# User_Control_Interface.net
KiCad netlist of a schematic drawn in Altium Designer
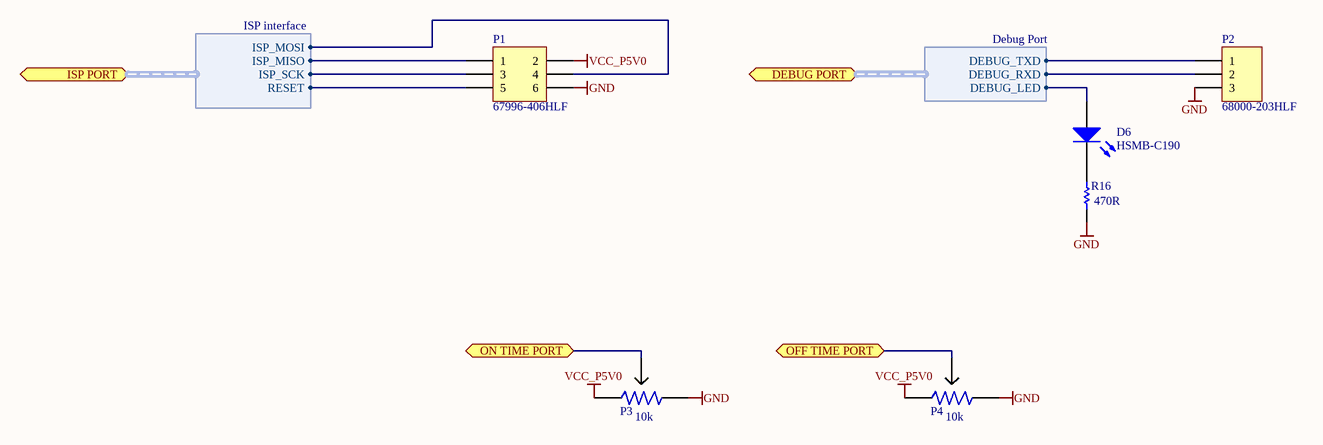
[diagram p0: User Control Interface.SchDoc]

(export (version "E")
  (design (tool "Eeschema 10.0.6"))
  (components
    (comp (ref "D6")
      (value "HSMB-C190")
      (footprint "1.6X0.8X0.8")
      (description "Blue Surface Mount Chip LED, Blue")
      (fields (field (name "PUBLISHER") "Altium Limited"))
      (libsource (lib "Avago Optoelectronic LED") (part "HSMB-C190"))
    )
    (comp (ref "P1")
      (value "67996-406HLF")
      (footprint "HDR2X3")
      (description "Header, 3-Pin, Dual row")
      (fields (field (name "PUBLISHER") "Altium Limited"))
      (libsource (lib "Miscellaneous Connectors") (part "Header 3X2"))
    )
    (comp (ref "P2")
      (value "68000-203HLF")
      (footprint "HDR1X3")
      (description "Header, 3-Pin")
      (fields (field (name "PUBLISHER") "Altium Limited"))
      (libsource (lib "Miscellaneous Connectors") (part "Header 3"))
    )
    (comp (ref "P3")
      (value "10k")
      (footprint "PS30-10PB10BRxxx")
      (description "slide potentiometer")
      (fields (field (name "Comment") "PS30-10PB10BR10K"))
      (libsource (lib "TT Electronics Slide Potentiometers") (part "PSxx-10PB10BRxxx"))
    )
    (comp (ref "P4")
      (value "10k")
      (footprint "PS30-10PB10BRxxx")
      (description "slide potentiometer")
      (fields (field (name "Comment") "PS30-10PB10BR10K"))
      (libsource (lib "TT Electronics Slide Potentiometers") (part "PSxx-10PB10BRxxx"))
    )
    (comp (ref "R16")
      (value "470R")
      (footprint "3-0603")
      (description "Thick Film Chip Resistor, 1 Ohm to 10M Ohm Range, 5% Tolerance, 0603 Size, 0.1 W")
      (fields (field (name "Comment") "ERJ3GEYJ471V") (field (name "PUBLISHER") "Altium Limited"))
      (libsource (lib "Panasonic Resistor") (part "ERJ3GE"))
    )
  )
  (nets
    (net (code "5") (name "/DEBUG_LED") (class "Default")
      (node (ref "D6") (pin "1") (pinfunction "A_1") (pintype "passive"))
    )
    (net (code "6") (name "/DEBUG_RXD") (class "Default")
      (node (ref "P2") (pin "2") (pinfunction "2_2") (pintype "passive"))
    )
    (net (code "7") (name "/DEBUG_TXD") (class "Default")
      (node (ref "P2") (pin "1") (pinfunction "1_1") (pintype "passive"))
    )
    (net (code "8") (name "/ISP_MISO") (class "Default")
      (node (ref "P1") (pin "1") (pinfunction "1_1") (pintype "passive"))
    )
    (net (code "9") (name "/ISP_MOSI") (class "Default")
      (node (ref "P1") (pin "4") (pinfunction "4_4") (pintype "passive"))
    )
    (net (code "10") (name "/ISP_SCK") (class "Default")
      (node (ref "P1") (pin "3") (pinfunction "3_3") (pintype "passive"))
    )
    (net (code "11") (name "/OFF TIME PORT") (class "Default")
      (node (ref "P4") (pin "2") (pinfunction "2_2") (pintype "passive"))
    )
    (net (code "12") (name "/ON TIME PORT") (class "Default")
      (node (ref "P3") (pin "2") (pinfunction "2_2") (pintype "passive"))
    )
    (net (code "13") (name "/RESET") (class "Default")
      (node (ref "P1") (pin "5") (pinfunction "5_5") (pintype "passive"))
    )
    (net (code "16") (name "GND") (class "Default")
      (node (ref "P1") (pin "6") (pinfunction "6_6") (pintype "passive"))
      (node (ref "P2") (pin "3") (pinfunction "3_3") (pintype "passive"))
      (node (ref "P3") (pin "3") (pinfunction "3_3") (pintype "passive"))
      (node (ref "P4") (pin "3") (pinfunction "3_3") (pintype "passive"))
      (node (ref "R16") (pin "1") (pinfunction "1_1") (pintype "passive"))
    )
    (net (code "17") (name "Net-(D6-K)") (class "Default")
      (node (ref "D6") (pin "2") (pinfunction "K_2") (pintype "passive"))
      (node (ref "R16") (pin "2") (pinfunction "2_2") (pintype "passive"))
    )
    (net (code "18") (name "VCC_P5V0") (class "Default")
      (node (ref "P1") (pin "2") (pinfunction "2_2") (pintype "passive"))
      (node (ref "P3") (pin "1") (pinfunction "1_1") (pintype "passive"))
      (node (ref "P4") (pin "1") (pinfunction "1_1") (pintype "passive"))
    )
  )
)
